# Peripherals.net
KiCad netlist of a schematic drawn in Altium Designer
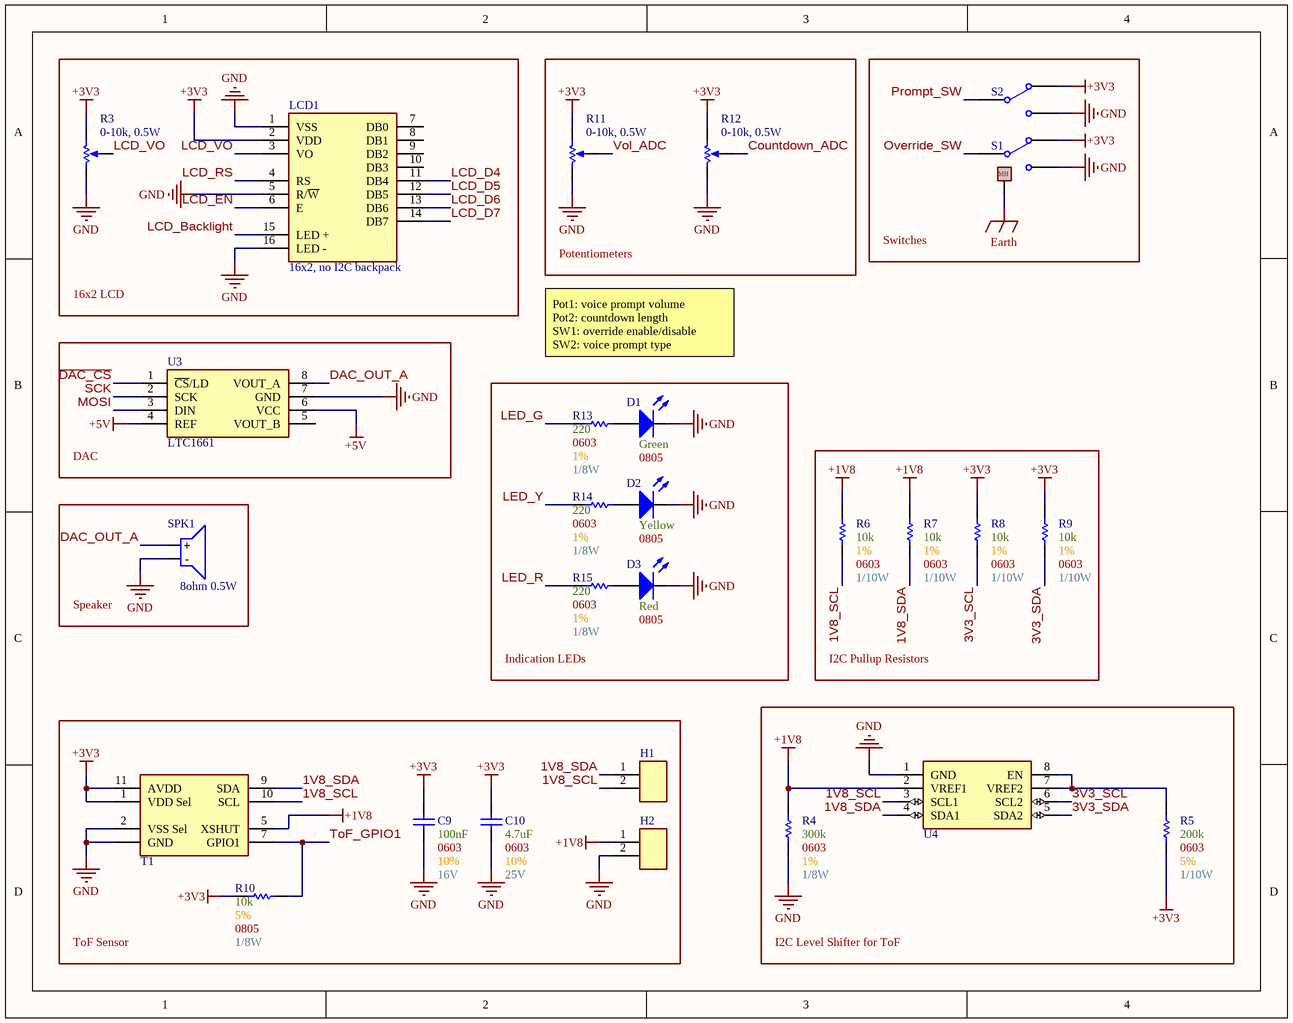
[diagram p0: Peripherals.SchDoc]

(export (version "E")
  (design (tool "Eeschema 10.0.6"))
  (components
    (comp (ref "C9")
      (value "[Cap] 0603 0.1uF 10% 16V")
      (footprint "[Cap] SMD 0603")
      (description "CC0603KRX7R7BB104")
      (fields
        (field (name "MAX VOLTAGE") "16V")
        (field (name "SIZE PACKAGE") "0603")
        (field (name "TOLERANCE") "10%")
        (field (name "CAPACITANCE") "100nF")
      )
      (libsource (lib "Capacitors") (part "[Cap] 0603 0.1uF 10% 16V"))
    )
    (comp (ref "C10")
      (value "[Cap] 0603 4.7uF 10% 25V")
      (footprint "[Cap] SMD 0603")
      (description "GRM188R61E475KE11D")
      (fields
        (field (name "MAX VOLTAGE") "25V")
        (field (name "SIZE PACKAGE") "0603")
        (field (name "TOLERANCE") "10%")
        (field (name "CAPACITANCE") "4.7uF")
      )
      (libsource (lib "Capacitors") (part "[Cap] 0603 4.7uF 10% 25V"))
    )
    (comp (ref "D1")
      (value "[LED] SMD 0805 Green")
      (footprint "[LED] SMD 0805")
      (description "LG R971-KN-1-0-20-R18")
      (fields (field (name "COLOR") "Green") (field (name "SIZE PACKAGE") "0805"))
      (libsource (lib "LEDs") (part "[LED] SMD 0805 Green"))
    )
    (comp (ref "D2")
      (value "[LED] SMD 0805 Yellow")
      (footprint "[LED] SMD 0805")
      (description "LY R976-PS-36-0-20-R18")
      (fields (field (name "COLOR") "Yellow") (field (name "SIZE PACKAGE") "0805"))
      (libsource (lib "LEDs") (part "[LED] SMD 0805 Yellow"))
    )
    (comp (ref "D3")
      (value "[LED] SMD 0805 Red")
      (footprint "[LED] SMD 0805")
      (description "LS R976-NR-1-0-20-R18")
      (fields (field (name "COLOR") "Red") (field (name "SIZE PACKAGE") "0805"))
      (libsource (lib "LEDs") (part "[LED] SMD 0805 Red"))
    )
    (comp (ref "H1")
      (value "1x2 Header")
      (footprint "[Header] 1x2 Male")
      (description "2.54mm pitch")
      (libsource (lib "Connectors") (part "[Header] 1x2 Male"))
    )
    (comp (ref "H2")
      (value "1x2 Header")
      (footprint "[Header] 1x2 Male")
      (description "2.54mm pitch")
      (libsource (lib "Connectors") (part "[Header] 1x2 Male"))
    )
    (comp (ref "LCD1")
      (value "16x2, no I2C backpack")
      (footprint "[LCD] 16x2 Parallel")
      (description "Sunfounder")
      (libsource (lib "Devices") (part "[LCD] 16x2 Parallel"))
    )
    (comp (ref "R3")
      (value "0-10k, 0.5W")
      (footprint "[Potentiometer] 10k 0.5W (2)")
      (description "3386T-1-103LF")
      (libsource (lib "Misc Components") (part "[Potentiometer] 10k 0.5W"))
    )
    (comp (ref "R4")
      (value "[300k] SMD 0603 1% 1/10W")
      (footprint "[Res] SMD 0603")
      (description "CRCW0603300KFKEA")
      (fields
        (field (name "WATTAGE") "1/8W")
        (field (name "TOLERANCE") "1%")
        (field (name "RESISTANCE") "300k")
        (field (name "SIZE PACKAGE") "0603")
      )
      (libsource (lib "Resistors") (part "[300k] SMD 0603 1% 1/10W"))
    )
    (comp (ref "R5")
      (value "[200k] SMD 0603 1% 1/10W")
      (footprint "[Res] SMD 0603")
      (description "RC0603JR-07200KL")
      (fields
        (field (name "WATTAGE") "1/10W")
        (field (name "TOLERANCE") "5%")
        (field (name "RESISTANCE") "200k")
        (field (name "SIZE PACKAGE") "0603")
      )
      (libsource (lib "Resistors") (part "[200k] SMD 0603 1% 1/10W"))
    )
    (comp (ref "R6")
      (value "[10k] SMD 0603 1% 1/8W")
      (footprint "[Res] SMD 0603")
      (description "RMCF0603FT10K0")
      (fields
        (field (name "WATTAGE") "1/10W")
        (field (name "TOLERANCE") "1%")
        (field (name "RESISTANCE") "10k")
        (field (name "SIZE PACKAGE") "0603")
      )
      (libsource (lib "Resistors") (part "[10k] SMD 0603 1% 1/8W"))
    )
    (comp (ref "R7")
      (value "[10k] SMD 0603 1% 1/8W")
      (footprint "[Res] SMD 0603")
      (description "RMCF0603FT10K0")
      (fields
        (field (name "WATTAGE") "1/10W")
        (field (name "TOLERANCE") "1%")
        (field (name "RESISTANCE") "10k")
        (field (name "SIZE PACKAGE") "0603")
      )
      (libsource (lib "Resistors") (part "[10k] SMD 0603 1% 1/8W"))
    )
    (comp (ref "R8")
      (value "[10k] SMD 0603 1% 1/8W")
      (footprint "[Res] SMD 0603")
      (description "RMCF0603FT10K0")
      (fields
        (field (name "WATTAGE") "1/10W")
        (field (name "TOLERANCE") "1%")
        (field (name "RESISTANCE") "10k")
        (field (name "SIZE PACKAGE") "0603")
      )
      (libsource (lib "Resistors") (part "[10k] SMD 0603 1% 1/8W"))
    )
    (comp (ref "R9")
      (value "[10k] SMD 0603 1% 1/8W")
      (footprint "[Res] SMD 0603")
      (description "RMCF0603FT10K0")
      (fields
        (field (name "WATTAGE") "1/10W")
        (field (name "TOLERANCE") "1%")
        (field (name "RESISTANCE") "10k")
        (field (name "SIZE PACKAGE") "0603")
      )
      (libsource (lib "Resistors") (part "[10k] SMD 0603 1% 1/8W"))
    )
    (comp (ref "R10")
      (value "[10k] SMD 0603 1% 1/8W")
      (footprint "[Res] SMD 0603")
      (description "RC0805JR-0710KL")
      (fields
        (field (name "WATTAGE") "1/8W")
        (field (name "TOLERANCE") "5%")
        (field (name "RESISTANCE") "10k")
        (field (name "SIZE PACKAGE") "0805")
      )
      (libsource (lib "Resistors") (part "[10k] SMD 0603 1% 1/8W"))
    )
    (comp (ref "R11")
      (value "0-10k, 0.5W")
      (footprint "[Potentiometer] 10k 0.5W (2)")
      (description "3386T-1-103LF")
      (libsource (lib "Misc Components") (part "[Potentiometer] 10k 0.5W"))
    )
    (comp (ref "R12")
      (value "0-10k, 0.5W")
      (footprint "[Potentiometer] 10k 0.5W (2)")
      (description "3386T-1-103LF")
      (libsource (lib "Misc Components") (part "[Potentiometer] 10k 0.5W"))
    )
    (comp (ref "R13")
      (value "[220] SMD 0603 1% 1/10W")
      (footprint "[Res] SMD 0603")
      (description "CRGCQ0805F220R")
      (fields
        (field (name "WATTAGE") "1/8W")
        (field (name "TOLERANCE") "1%")
        (field (name "RESISTANCE") "220")
        (field (name "SIZE PACKAGE") "0603")
      )
      (libsource (lib "Resistors") (part "[220] SMD 0603 1% 1/10W"))
    )
    (comp (ref "R14")
      (value "[220] SMD 0603 1% 1/10W")
      (footprint "[Res] SMD 0603")
      (description "CRGCQ0805F220R")
      (fields
        (field (name "WATTAGE") "1/8W")
        (field (name "TOLERANCE") "1%")
        (field (name "RESISTANCE") "220")
        (field (name "SIZE PACKAGE") "0603")
      )
      (libsource (lib "Resistors") (part "[220] SMD 0603 1% 1/10W"))
    )
    (comp (ref "R15")
      (value "[220] SMD 0603 1% 1/10W")
      (footprint "[Res] SMD 0603")
      (description "CRGCQ0805F220R")
      (fields
        (field (name "WATTAGE") "1/8W")
        (field (name "TOLERANCE") "1%")
        (field (name "RESISTANCE") "220")
        (field (name "SIZE PACKAGE") "0603")
      )
      (libsource (lib "Resistors") (part "[220] SMD 0603 1% 1/10W"))
    )
    (comp (ref "S1")
      (value "[SPDT] Toggle")
      (footprint "[SPDT] Toggle")
      (description "ANT11TFHQE")
      (libsource (lib "Switches") (part "[SPDT] Toggle"))
    )
    (comp (ref "S2")
      (value "[SPDT] Slide Switch")
      (footprint "[SPDT] Slide Switch")
      (description "09.03290.01")
      (libsource (lib "Switches") (part "[SPDT] Slide Switch"))
    )
    (comp (ref "SPK1")
      (value "8ohm 0.5W")
      (footprint "[Speaker] 8ohm 0.5W")
      (description "CMS-40558N-L152")
      (libsource (lib "Misc Components") (part "[Speaker] 8ohm 0.5W"))
    )
    (comp (ref "T1")
      (value "[ToF] VL53L1X")
      (footprint "[ToF] VL53L1X")
      (description "VL53L1CXV0FY/1")
      (libsource (lib "Devices") (part "[ToF] VL53L1X"))
    )
    (comp (ref "U3")
      (value "LTC1661")
      (footprint "[DAC] LTC1661")
      (description "LTC1661CN8#PBF")
      (libsource (lib "ICs") (part "[DAC] LTC1661"))
    )
    (comp (ref "U4")
      (value "[Level Shifter] I2C Level Shifter")
      (footprint "[Level Shifter] I2C Level Shifter")
      (description "PCA9306DCTR")
      (libsource (lib "ICs") (part "[Level Shifter] I2C Level Shifter"))
    )
  )
  (nets
    (net (code "1") (name "+1V8") (class "Default")
      (node (ref "H2") (pin "1") (pintype "passive"))
      (node (ref "R4") (pin "2") (pinfunction "2_2") (pintype "passive"))
      (node (ref "R6") (pin "2") (pinfunction "2_2") (pintype "passive"))
      (node (ref "R7") (pin "2") (pinfunction "2_2") (pintype "passive"))
      (node (ref "T1") (pin "5") (pinfunction "XSHUT_5") (pintype "passive"))
      (node (ref "U4") (pin "2") (pinfunction "VREF1_2") (pintype "power_in"))
    )
    (net (code "2") (name "+3V3") (class "Default")
      (node (ref "C10") (pin "2") (pinfunction "2_2") (pintype "passive"))
      (node (ref "C9") (pin "2") (pinfunction "2_2") (pintype "passive"))
      (node (ref "LCD1") (pin "2") (pinfunction "VDD_2") (pintype "passive"))
      (node (ref "R10") (pin "2") (pinfunction "2_2") (pintype "passive"))
      (node (ref "R11") (pin "1") (pinfunction "TOP_1") (pintype "passive"))
      (node (ref "R12") (pin "1") (pinfunction "TOP_1") (pintype "passive"))
      (node (ref "R3") (pin "1") (pinfunction "TOP_1") (pintype "passive"))
      (node (ref "R5") (pin "1") (pinfunction "1_1") (pintype "passive"))
      (node (ref "R8") (pin "2") (pinfunction "2_2") (pintype "passive"))
      (node (ref "R9") (pin "2") (pinfunction "2_2") (pintype "passive"))
      (node (ref "S1") (pin "3") (pinfunction "3_3") (pintype "passive"))
      (node (ref "S2") (pin "3") (pinfunction "3_3") (pintype "passive"))
      (node (ref "T1") (pin "1") (pinfunction "VDD_Sel_1") (pintype "power_in"))
      (node (ref "T1") (pin "11") (pinfunction "AVDD_11") (pintype "power_in"))
    )
    (net (code "3") (name "+5V") (class "Default")
      (node (ref "U3") (pin "4") (pinfunction "REF_4") (pintype "passive"))
      (node (ref "U3") (pin "6") (pinfunction "VCC_6") (pintype "passive"))
    )
    (net (code "4") (name "/1V8_SCL") (class "Default")
      (node (ref "H1") (pin "2") (pintype "passive"))
      (node (ref "R6") (pin "1") (pinfunction "1_1") (pintype "passive"))
      (node (ref "T1") (pin "10") (pinfunction "SCL_10") (pintype "passive"))
      (node (ref "U4") (pin "3") (pinfunction "SCL1_3") (pintype "bidirectional"))
    )
    (net (code "5") (name "/1V8_SDA") (class "Default")
      (node (ref "H1") (pin "1") (pintype "passive"))
      (node (ref "R7") (pin "1") (pinfunction "1_1") (pintype "passive"))
      (node (ref "T1") (pin "9") (pinfunction "SDA_9") (pintype "passive"))
      (node (ref "U4") (pin "4") (pinfunction "SDA1_4") (pintype "bidirectional"))
    )
    (net (code "6") (name "/3V3_SCL") (class "Default")
      (node (ref "R8") (pin "1") (pinfunction "1_1") (pintype "passive"))
      (node (ref "U4") (pin "6") (pinfunction "SCL2_6") (pintype "bidirectional"))
    )
    (net (code "7") (name "/3V3_SDA") (class "Default")
      (node (ref "R9") (pin "1") (pinfunction "1_1") (pintype "passive"))
      (node (ref "U4") (pin "5") (pinfunction "SDA2_5") (pintype "bidirectional"))
    )
    (net (code "8") (name "/Countdown_ADC") (class "Default")
      (node (ref "R12") (pin "2") (pinfunction "TAP_2") (pintype "passive"))
    )
    (net (code "9") (name "/DAC_CS") (class "Default")
      (node (ref "U3") (pin "1") (pinfunction "~{CS}/LD_1") (pintype "passive"))
    )
    (net (code "10") (name "/DAC_OUT_A") (class "Default")
      (node (ref "SPK1") (pin "1") (pinfunction "+_1") (pintype "power_in"))
      (node (ref "U3") (pin "8") (pinfunction "VOUT_A_8") (pintype "passive"))
    )
    (net (code "11") (name "/LCD_Backlight") (class "Default")
      (node (ref "LCD1") (pin "15") (pinfunction "LED_+_15") (pintype "passive"))
    )
    (net (code "12") (name "/LCD_D4") (class "Default")
      (node (ref "LCD1") (pin "11") (pinfunction "DB4_11") (pintype "passive"))
    )
    (net (code "13") (name "/LCD_D5") (class "Default")
      (node (ref "LCD1") (pin "12") (pinfunction "DB5_12") (pintype "passive"))
    )
    (net (code "14") (name "/LCD_D6") (class "Default")
      (node (ref "LCD1") (pin "13") (pinfunction "DB6_13") (pintype "passive"))
    )
    (net (code "15") (name "/LCD_D7") (class "Default")
      (node (ref "LCD1") (pin "14") (pinfunction "DB7_14") (pintype "passive"))
    )
    (net (code "16") (name "/LCD_EN") (class "Default")
      (node (ref "LCD1") (pin "6") (pinfunction "E_6") (pintype "passive"))
    )
    (net (code "17") (name "/LCD_RS") (class "Default")
      (node (ref "LCD1") (pin "4") (pinfunction "RS_4") (pintype "passive"))
    )
    (net (code "18") (name "/LCD_VO") (class "Default")
      (node (ref "LCD1") (pin "3") (pinfunction "VO_3") (pintype "passive"))
      (node (ref "R3") (pin "2") (pinfunction "TAP_2") (pintype "passive"))
    )
    (net (code "19") (name "/LED_G") (class "Default")
      (node (ref "R13") (pin "1") (pinfunction "1_1") (pintype "passive"))
    )
    (net (code "20") (name "/LED_R") (class "Default")
      (node (ref "R15") (pin "1") (pinfunction "1_1") (pintype "passive"))
    )
    (net (code "21") (name "/LED_Y") (class "Default")
      (node (ref "R14") (pin "1") (pinfunction "1_1") (pintype "passive"))
    )
    (net (code "22") (name "/MOSI") (class "Default")
      (node (ref "U3") (pin "3") (pinfunction "DIN_3") (pintype "passive"))
    )
    (net (code "23") (name "/Override_SW") (class "Default")
      (node (ref "S1") (pin "2") (pinfunction "2_2") (pintype "passive"))
    )
    (net (code "24") (name "/Prompt_SW") (class "Default")
      (node (ref "S2") (pin "2") (pinfunction "2_2") (pintype "passive"))
    )
    (net (code "25") (name "/SCK") (class "Default")
      (node (ref "U3") (pin "2") (pinfunction "SCK_2") (pintype "passive"))
    )
    (net (code "26") (name "/ToF_GPIO1") (class "Default")
      (node (ref "R10") (pin "1") (pinfunction "1_1") (pintype "passive"))
      (node (ref "T1") (pin "7") (pinfunction "GPIO1_7") (pintype "passive"))
    )
    (net (code "27") (name "/Vol_ADC") (class "Default")
      (node (ref "R11") (pin "2") (pinfunction "TAP_2") (pintype "passive"))
    )
    (net (code "28") (name "Earth") (class "Default")
      (node (ref "S1") (pin "X") (pinfunction "Mount_Hole_X") (pintype "passive"))
    )
    (net (code "29") (name "GND") (class "Default")
      (node (ref "C10") (pin "1") (pinfunction "1_1") (pintype "passive"))
      (node (ref "C9") (pin "1") (pinfunction "1_1") (pintype "passive"))
      (node (ref "D1") (pin "2") (pinfunction "Cathode_2") (pintype "passive"))
      (node (ref "D2") (pin "2") (pinfunction "Cathode_2") (pintype "passive"))
      (node (ref "D3") (pin "2") (pinfunction "Cathode_2") (pintype "passive"))
      (node (ref "H2") (pin "2") (pintype "passive"))
      (node (ref "LCD1") (pin "1") (pinfunction "VSS_1") (pintype "passive"))
      (node (ref "LCD1") (pin "16") (pinfunction "LED_-_16") (pintype "passive"))
      (node (ref "LCD1") (pin "5") (pinfunction "R/~{W}_5") (pintype "passive"))
      (node (ref "R11") (pin "3") (pinfunction "BOT_3") (pintype "passive"))
      (node (ref "R12") (pin "3") (pinfunction "BOT_3") (pintype "passive"))
      (node (ref "R3") (pin "3") (pinfunction "BOT_3") (pintype "passive"))
      (node (ref "R4") (pin "1") (pinfunction "1_1") (pintype "passive"))
      (node (ref "S1") (pin "1") (pinfunction "1_1") (pintype "passive"))
      (node (ref "S2") (pin "1") (pinfunction "1_1") (pintype "passive"))
      (node (ref "SPK1") (pin "2") (pinfunction "-_2") (pintype "power_in"))
      (node (ref "T1") (pin "2") (pinfunction "VSS_Sel_2") (pintype "power_in"))
      (node (ref "T1") (pin "GND") (pinfunction "GND_GND") (pintype "power_in"))
      (node (ref "U3") (pin "7") (pinfunction "GND_7") (pintype "passive"))
      (node (ref "U4") (pin "1") (pinfunction "GND_1") (pintype "power_in"))
    )
    (net (code "30") (name "Net-(D1-Anode)") (class "Default")
      (node (ref "D1") (pin "1") (pinfunction "Anode_1") (pintype "passive"))
      (node (ref "R13") (pin "2") (pinfunction "2_2") (pintype "passive"))
    )
    (net (code "31") (name "Net-(D2-Anode)") (class "Default")
      (node (ref "D2") (pin "1") (pinfunction "Anode_1") (pintype "passive"))
      (node (ref "R14") (pin "2") (pinfunction "2_2") (pintype "passive"))
    )
    (net (code "32") (name "Net-(D3-Anode)") (class "Default")
      (node (ref "D3") (pin "1") (pinfunction "Anode_1") (pintype "passive"))
      (node (ref "R15") (pin "2") (pinfunction "2_2") (pintype "passive"))
    )
    (net (code "33") (name "Net-(U4-EN)") (class "Default")
      (node (ref "R5") (pin "2") (pinfunction "2_2") (pintype "passive"))
      (node (ref "U4") (pin "7") (pinfunction "VREF2_7") (pintype "power_in"))
      (node (ref "U4") (pin "8") (pinfunction "EN_8") (pintype "passive"))
    )
    (net (code "34") (name "unconnected-(LCD1-DB0-Pad7)") (class "Default")
      (node (ref "LCD1") (pin "7") (pinfunction "DB0_7") (pintype "passive"))
    )
    (net (code "35") (name "unconnected-(LCD1-DB1-Pad8)") (class "Default")
      (node (ref "LCD1") (pin "8") (pinfunction "DB1_8") (pintype "passive"))
    )
    (net (code "36") (name "unconnected-(LCD1-DB2-Pad9)") (class "Default")
      (node (ref "LCD1") (pin "9") (pinfunction "DB2_9") (pintype "passive"))
    )
    (net (code "37") (name "unconnected-(LCD1-DB3-Pad10)") (class "Default")
      (node (ref "LCD1") (pin "10") (pinfunction "DB3_10") (pintype "passive"))
    )
    (net (code "38") (name "unconnected-(U3-VOUT_B-Pad5)") (class "Default")
      (node (ref "U3") (pin "5") (pinfunction "VOUT_B_5") (pintype "passive"))
    )
  )
)
